# Optical_TX.net
KiCad netlist of a schematic drawn in Altium Designer
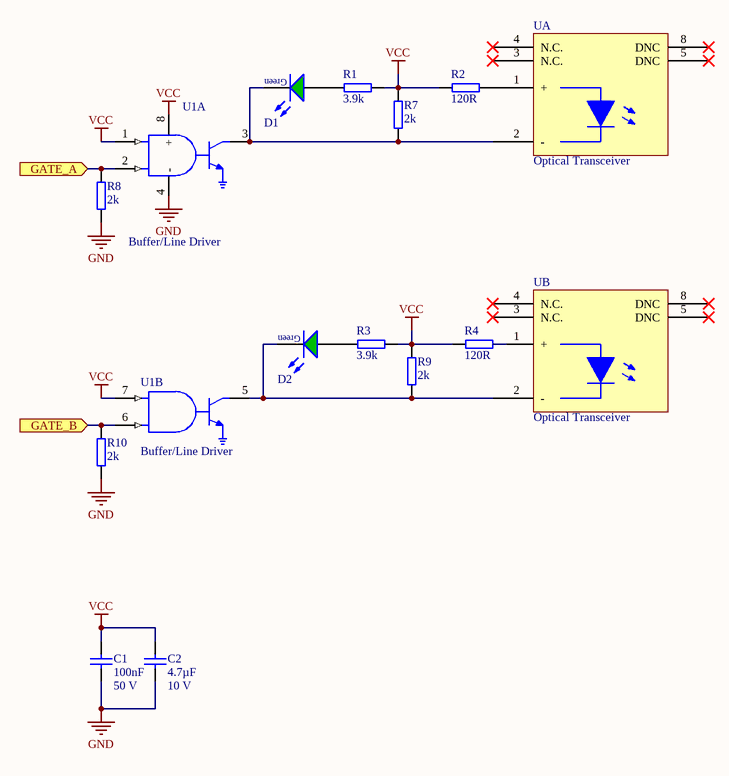
[diagram p0: Optical_TX.SchDoc]

(export (version "E")
  (design (tool "Eeschema 10.0.6"))
  (components
    (comp (ref "C1")
      (value "100nF")
      (footprint "C_0603(1608)100_L")
      (description "CAP 0603 (1608 Metric) SMD")
      (fields
        (field (name "TOLERANCE") "±20%")
        (field (name "MF") "Yageo")
        (field (name "VOLTAGE") "50 V")
        (field (name "CREATED") "2018_09_06_AGeiger")
      )
      (libsource (lib "UZOhm_Optical") (part "C_0603"))
    )
    (comp (ref "C2")
      (value "4.7µF")
      (footprint "CAP_2012X06N")
      (description "CAP 0805 (2012 Metric) SMD")
      (fields
        (field (name "TOLERANCE") "±10%")
        (field (name "MF") "Taiyo Yuden")
        (field (name "RATED VOLTAGE") "10 V")
        (field (name "CREATED") "2018_09_06_AGeiger")
      )
      (libsource (lib "UZOhm_Optical") (part "C_0805"))
    )
    (comp (ref "D1")
      (value "150060GS75000")
      (footprint "WL-SMCW_0603")
      (description "WL-SMCW SMD Mono-color Chip LED Waterclear, size 0603, Green, 3.2 V, 140°")
      (fields (field (name "MF") "Wuerth Elektronik") (field (name "CREATED") "2018_09_06_AGeiger"))
      (libsource (lib "UZOhm_Optical") (part "LED_Green_0603"))
    )
    (comp (ref "D2")
      (value "150060GS75000")
      (footprint "WL-SMCW_0603")
      (description "WL-SMCW SMD Mono-color Chip LED Waterclear, size 0603, Green, 3.2 V, 140°")
      (fields (field (name "MF") "Wuerth Elektronik") (field (name "CREATED") "2018_09_06_AGeiger"))
      (libsource (lib "UZOhm_Optical") (part "LED_Green_0603"))
    )
    (comp (ref "R1")
      (value "3.9k")
      (footprint "R_0603_N")
      (description "SMD Resistor 0603")
      (fields
        (field (name "TOLERANCE") "1%")
        (field (name "VOLTAGE") "75V")
        (field (name "CREATED") "2018_09_06_AGeiger")
      )
      (libsource (lib "UZOhm_Optical") (part "R_0603"))
    )
    (comp (ref "R2")
      (value "120R")
      (footprint "RES_2012X06N")
      (description "SMD Resistor 0805")
      (fields (field (name "MF") "Bourns") (field (name "MPN") "CR0805-FX-1200ELF"))
      (libsource (lib "UZOhm_Optical") (part "R_0805"))
    )
    (comp (ref "R3")
      (value "3.9k")
      (footprint "R_0603_N")
      (description "SMD Resistor 0603")
      (fields
        (field (name "TOLERANCE") "1%")
        (field (name "VOLTAGE") "75V")
        (field (name "CREATED") "2018_09_06_AGeiger")
      )
      (libsource (lib "UZOhm_Optical") (part "R_0603"))
    )
    (comp (ref "R4")
      (value "120R")
      (footprint "RES_2012X06N")
      (description "SMD Resistor 0805")
      (fields (field (name "MF") "Bourns") (field (name "MPN") "CR0805-FX-1200ELF"))
      (libsource (lib "UZOhm_Optical") (part "R_0805"))
    )
    (comp (ref "R7")
      (value "2k")
      (footprint "R_0603_N")
      (description "SMD Resistor 0603")
      (fields
        (field (name "TOLERANCE") "1%")
        (field (name "VOLTAGE") "75 V")
        (field (name "CREATED") "2018_09_06_AGeiger")
      )
      (libsource (lib "UZOhm_Optical") (part "R_0603"))
    )
    (comp (ref "R8")
      (value "2k")
      (footprint "R_0603_N")
      (description "SMD Resistor 0603")
      (fields
        (field (name "TOLERANCE") "1%")
        (field (name "VOLTAGE") "75 V")
        (field (name "CREATED") "2018_09_06_AGeiger")
      )
      (libsource (lib "UZOhm_Optical") (part "R_0603"))
    )
    (comp (ref "R9")
      (value "2k")
      (footprint "R_0603_N")
      (description "SMD Resistor 0603")
      (fields
        (field (name "TOLERANCE") "1%")
        (field (name "VOLTAGE") "75 V")
        (field (name "CREATED") "2018_09_06_AGeiger")
      )
      (libsource (lib "UZOhm_Optical") (part "R_0603"))
    )
    (comp (ref "R10")
      (value "2k")
      (footprint "R_0603_N")
      (description "SMD Resistor 0603")
      (fields
        (field (name "TOLERANCE") "1%")
        (field (name "VOLTAGE") "75 V")
        (field (name "CREATED") "2018_09_06_AGeiger")
      )
      (libsource (lib "UZOhm_Optical") (part "R_0603"))
    )
    (comp (ref "U1")
      (value "Buffer/Line Driver")
      (footprint "SOIC127P600X175-8N")
      (description "Buffers & Line Drivers Dual Very-HS HC Peripheral Drivers")
      (fields
        (field (name "MF") "Texas Instruments")
        (field (name "MPN") "SN75452BDR")
        (field (name "CREATED") "2019_04_09_Kreppel")
      )
      (libsource (lib "UZOhm_Optical") (part "SN75452BDR"))
    )
    (comp (ref "UA")
      (value "Optical Transceiver")
      (footprint "HFBRx5XX")
      (description "Fibre Optic Transmitters, Receivers, Transceivers Versatile Link Horiz 5MBd Tx RoHS")
      (fields
        (field (name "MF") "Broadcom/Avago")
        (field (name "MPN") "HFBR-1521Z")
        (field (name "CREATED") "2019_04_09_Kreppel")
      )
      (libsource (lib "UZOhm_Optical") (part "HFBR-1521Z"))
    )
    (comp (ref "UB")
      (value "Optical Transceiver")
      (footprint "HFBRx5XX")
      (description "Fibre Optic Transmitters, Receivers, Transceivers Versatile Link Horiz 5MBd Tx RoHS")
      (fields
        (field (name "MF") "Broadcom/Avago")
        (field (name "MPN") "HFBR-1521Z")
        (field (name "CREATED") "2019_04_09_Kreppel")
      )
      (libsource (lib "UZOhm_Optical") (part "HFBR-1521Z"))
    )
  )
  (nets
    (net (code "1") (name "/GATE_A") (class "Default")
      (node (ref "R8") (pin "2") (pinfunction "2_2") (pintype "passive"))
      (node (ref "U1") (pin "2") (pinfunction "1B_2") (pintype "input"))
    )
    (net (code "2") (name "/GATE_B") (class "Default")
      (node (ref "R10") (pin "2") (pinfunction "2_2") (pintype "passive"))
      (node (ref "U1") (pin "6") (pinfunction "2A_6") (pintype "input"))
    )
    (net (code "3") (name "GND") (class "Default")
      (node (ref "C1") (pin "2") (pinfunction "2_2") (pintype "passive"))
      (node (ref "C2") (pin "2") (pinfunction "2_2") (pintype "passive"))
      (node (ref "R10") (pin "1") (pinfunction "1_1") (pintype "passive"))
      (node (ref "R8") (pin "1") (pinfunction "1_1") (pintype "passive"))
      (node (ref "U1") (pin "4") (pinfunction "-_4") (pintype "power_in"))
    )
    (net (code "4") (name "Net-(D1-A)") (class "Default")
      (node (ref "D1") (pin "2") (pinfunction "A_2") (pintype "passive"))
      (node (ref "R1") (pin "1") (pinfunction "1_1") (pintype "passive"))
    )
    (net (code "5") (name "Net-(D1-K)") (class "Default")
      (node (ref "D1") (pin "1") (pinfunction "K_1") (pintype "passive"))
      (node (ref "R7") (pin "1") (pinfunction "1_1") (pintype "passive"))
      (node (ref "U1") (pin "3") (pinfunction "1Y_3") (pintype "open_collector"))
      (node (ref "UA") (pin "2") (pinfunction "-_2") (pintype "passive"))
    )
    (net (code "6") (name "Net-(D2-A)") (class "Default")
      (node (ref "D2") (pin "2") (pinfunction "A_2") (pintype "passive"))
      (node (ref "R3") (pin "2") (pinfunction "2_2") (pintype "passive"))
    )
    (net (code "7") (name "Net-(D2-K)") (class "Default")
      (node (ref "D2") (pin "1") (pinfunction "K_1") (pintype "passive"))
      (node (ref "R9") (pin "1") (pinfunction "1_1") (pintype "passive"))
      (node (ref "U1") (pin "5") (pinfunction "2Y_5") (pintype "open_collector"))
      (node (ref "UB") (pin "2") (pinfunction "-_2") (pintype "passive"))
    )
    (net (code "8") (name "Net-(UA-+)") (class "Default")
      (node (ref "R2") (pin "2") (pintype "passive"))
      (node (ref "UA") (pin "1") (pinfunction "+_1") (pintype "passive"))
    )
    (net (code "9") (name "Net-(UB-+)") (class "Default")
      (node (ref "R4") (pin "2") (pintype "passive"))
      (node (ref "UB") (pin "1") (pinfunction "+_1") (pintype "passive"))
    )
    (net (code "10") (name "VCC") (class "Default")
      (node (ref "C1") (pin "1") (pinfunction "1_1") (pintype "passive"))
      (node (ref "C2") (pin "1") (pinfunction "1_1") (pintype "passive"))
      (node (ref "R1") (pin "2") (pinfunction "2_2") (pintype "passive"))
      (node (ref "R2") (pin "1") (pintype "passive"))
      (node (ref "R3") (pin "1") (pinfunction "1_1") (pintype "passive"))
      (node (ref "R4") (pin "1") (pintype "passive"))
      (node (ref "R7") (pin "2") (pinfunction "2_2") (pintype "passive"))
      (node (ref "R9") (pin "2") (pinfunction "2_2") (pintype "passive"))
      (node (ref "U1") (pin "1") (pinfunction "1A_1") (pintype "input"))
      (node (ref "U1") (pin "7") (pinfunction "2B_7") (pintype "input"))
      (node (ref "U1") (pin "8") (pinfunction "+_8") (pintype "power_in"))
    )
    (net (code "11") (name "unconnected-(UA-DNC-Pad5)") (class "Default")
      (node (ref "UA") (pin "5") (pinfunction "DNC_5") (pintype "passive+no_connect"))
    )
    (net (code "12") (name "unconnected-(UA-DNC-Pad8)") (class "Default")
      (node (ref "UA") (pin "8") (pinfunction "DNC_8") (pintype "passive+no_connect"))
    )
    (net (code "13") (name "unconnected-(UA-N.C.-Pad3)") (class "Default")
      (node (ref "UA") (pin "3") (pinfunction "N.C._3") (pintype "passive+no_connect"))
    )
    (net (code "14") (name "unconnected-(UA-N.C.-Pad4)") (class "Default")
      (node (ref "UA") (pin "4") (pinfunction "N.C._4") (pintype "passive+no_connect"))
    )
    (net (code "15") (name "unconnected-(UB-DNC-Pad5)") (class "Default")
      (node (ref "UB") (pin "5") (pinfunction "DNC_5") (pintype "passive+no_connect"))
    )
    (net (code "16") (name "unconnected-(UB-DNC-Pad8)") (class "Default")
      (node (ref "UB") (pin "8") (pinfunction "DNC_8") (pintype "passive+no_connect"))
    )
    (net (code "17") (name "unconnected-(UB-N.C.-Pad3)") (class "Default")
      (node (ref "UB") (pin "3") (pinfunction "N.C._3") (pintype "passive+no_connect"))
    )
    (net (code "18") (name "unconnected-(UB-N.C.-Pad4)") (class "Default")
      (node (ref "UB") (pin "4") (pinfunction "N.C._4") (pintype "passive+no_connect"))
    )
  )
)
